# LDBiasDriver_CC_v2.net
KiCad netlist of a schematic drawn in EAGLE
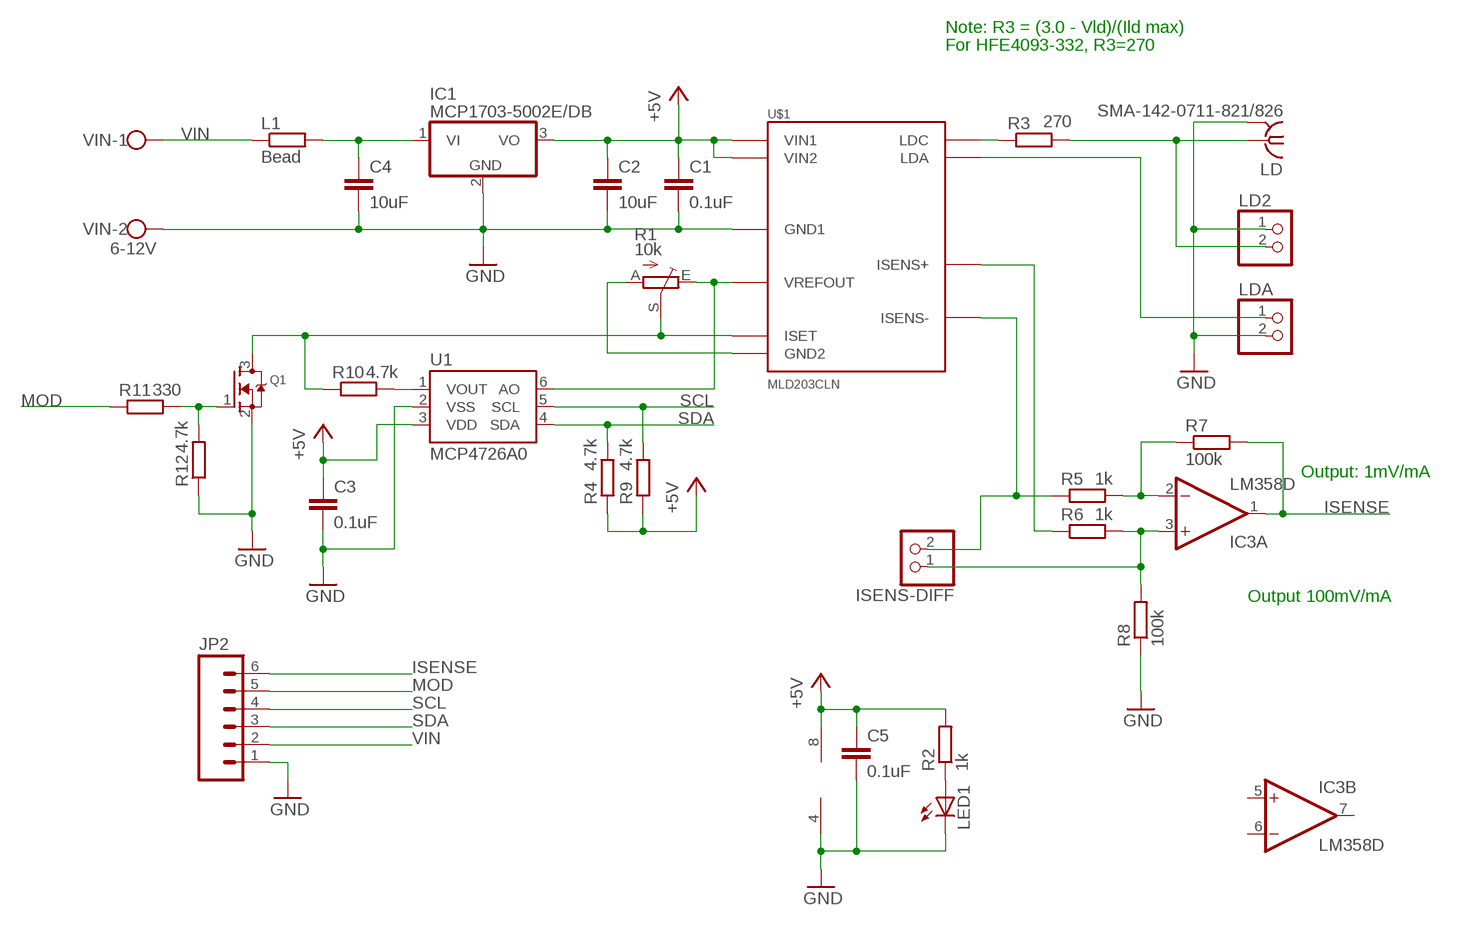
[diagram p0: schematic, sheet 1]

(export (version "E")
  (design (tool "Eeschema 10.0.6"))
  (components
    (comp (ref "C1")
      (value "0.1uF")
      (footprint "eagle-import:C0805")
      (libsource (lib "eagle-import") (part "C-EUC0805"))
    )
    (comp (ref "C2")
      (value "10uF")
      (footprint "eagle-import:C0805")
      (libsource (lib "eagle-import") (part "C-EUC0805"))
    )
    (comp (ref "C3")
      (value "0.1uF")
      (footprint "eagle-import:C0805")
      (libsource (lib "eagle-import") (part "C-EUC0805"))
    )
    (comp (ref "C4")
      (value "10uF")
      (footprint "eagle-import:C0805")
      (libsource (lib "eagle-import") (part "C-EUC0805"))
    )
    (comp (ref "C5")
      (value "0.1uF")
      (footprint "eagle-import:C0805")
      (libsource (lib "eagle-import") (part "C-EUC0805"))
    )
    (comp (ref "IC1")
      (value "MCP1703-5002E/DB")
      (footprint "eagle-import:SOT223")
      (libsource (lib "eagle-import") (part "MCP1703DB"))
    )
    (comp (ref "IC3")
      (value "LM358D")
      (footprint "eagle-import:SO08")
      (libsource (lib "eagle-import") (part "LM358D"))
    )
    (comp (ref "ISENS-DIFF")
      (value "PINHD-1X2")
      (footprint "eagle-import:1X02")
      (libsource (lib "eagle-import") (part "PINHD-1X2"))
    )
    (comp (ref "JP2")
      (value "M06POLAR_LOCK")
      (footprint "eagle-import:MOLEX-1X6_LOCK")
      (libsource (lib "eagle-import") (part "M06POLAR_LOCK"))
    )
    (comp (ref "L1")
      (value "Bead")
      (footprint "eagle-import:R0805")
      (libsource (lib "eagle-import") (part "R-EU_R0805"))
    )
    (comp (ref "LD")
      (value "SMA-142-0711-821/826")
      (footprint "eagle-import:J502-ND-142-0711-821_826")
      (fields (field (name "MF") "JOHNSON COMPONENTS") (field (name "MPN") "142-0711-821"))
      (libsource (lib "eagle-import") (part "SMA-142-0711-821/826"))
    )
    (comp (ref "LD2")
      (value "PINHD-1X2")
      (footprint "eagle-import:1X02")
      (libsource (lib "eagle-import") (part "PINHD-1X2"))
    )
    (comp (ref "LDA")
      (value "PINHD-1X2")
      (footprint "eagle-import:1X02")
      (libsource (lib "eagle-import") (part "PINHD-1X2"))
    )
    (comp (ref "LED1")
      (value "LEDCHIPLED_1206")
      (footprint "eagle-import:CHIPLED_1206")
      (libsource (lib "eagle-import") (part "LEDCHIPLED_1206"))
    )
    (comp (ref "Q1")
      (value "MOSFET-NREFLOW")
      (footprint "eagle-import:SOT23")
      (libsource (lib "eagle-import") (part "MOSFET-NREFLOW"))
    )
    (comp (ref "R1")
      (value "10k")
      (footprint "eagle-import:RJ9W")
      (libsource (lib "eagle-import") (part "TRIM_EU-RJ9W"))
    )
    (comp (ref "R2")
      (value "1k")
      (footprint "eagle-import:R0805")
      (libsource (lib "eagle-import") (part "R-EU_R0805"))
    )
    (comp (ref "R3")
      (value "270")
      (footprint "eagle-import:R0805")
      (libsource (lib "eagle-import") (part "R-EU_R0805"))
    )
    (comp (ref "R4")
      (value "4.7k")
      (footprint "eagle-import:R0805")
      (libsource (lib "eagle-import") (part "R-EU_R0805"))
    )
    (comp (ref "R5")
      (value "1k")
      (footprint "eagle-import:R0805")
      (libsource (lib "eagle-import") (part "R-EU_R0805"))
    )
    (comp (ref "R6")
      (value "1k")
      (footprint "eagle-import:R0805")
      (libsource (lib "eagle-import") (part "R-EU_R0805"))
    )
    (comp (ref "R7")
      (value "100k")
      (footprint "eagle-import:R0805")
      (libsource (lib "eagle-import") (part "R-EU_R0805"))
    )
    (comp (ref "R8")
      (value "100k")
      (footprint "eagle-import:R0805")
      (libsource (lib "eagle-import") (part "R-EU_R0805"))
    )
    (comp (ref "R9")
      (value "4.7k")
      (footprint "eagle-import:R0805")
      (libsource (lib "eagle-import") (part "R-EU_R0805"))
    )
    (comp (ref "R10")
      (value "4.7k")
      (footprint "eagle-import:R0805")
      (libsource (lib "eagle-import") (part "R-EU_R0805"))
    )
    (comp (ref "R11")
      (value "330")
      (footprint "eagle-import:R0805")
      (libsource (lib "eagle-import") (part "R-EU_R0805"))
    )
    (comp (ref "R12")
      (value "4.7k")
      (footprint "eagle-import:R0805")
      (libsource (lib "eagle-import") (part "R-EU_R0805"))
    )
    (comp (ref "U$1")
      (value "MLD203CLN")
      (footprint "eagle-import:MLD203")
      (libsource (lib "eagle-import") (part "MLD203CLN"))
    )
    (comp (ref "U1")
      (value "MCP4726A0")
      (footprint "eagle-import:SOT23-6")
      (libsource (lib "eagle-import") (part "MCP4725SOT-23"))
    )
    (comp (ref "VIN")
      (value "6-12V")
      (footprint "eagle-import:W237-102")
      (fields (field (name "MPN") "237-102"))
      (libsource (lib "eagle-import") (part "W237-102"))
    )
  )
  (nets
    (net (code "1") (name "+5V") (class "Default")
      (node (ref "C1") (pin "1") (pinfunction "1_1") (pintype "passive"))
      (node (ref "C2") (pin "1") (pinfunction "1_1") (pintype "passive"))
      (node (ref "C3") (pin "1") (pinfunction "1_1") (pintype "passive"))
      (node (ref "C5") (pin "1") (pinfunction "1_1") (pintype "passive"))
      (node (ref "IC1") (pin "3") (pinfunction "VO_3") (pintype "passive"))
      (node (ref "IC3") (pin "8") (pinfunction "V+_8") (pintype "power_in"))
      (node (ref "R2") (pin "2") (pinfunction "2_2") (pintype "passive"))
      (node (ref "R4") (pin "1") (pinfunction "1_1") (pintype "passive"))
      (node (ref "R9") (pin "1") (pinfunction "1_1") (pintype "passive"))
      (node (ref "U$1") (pin "P$1") (pinfunction "VIN1_P$1") (pintype "power_in"))
      (node (ref "U$1") (pin "P$2") (pinfunction "VIN2_P$2") (pintype "power_in"))
      (node (ref "U1") (pin "3") (pinfunction "VDD_3") (pintype "bidirectional"))
    )
    (net (code "2") (name "/ISENSE") (class "Default")
      (node (ref "IC3") (pin "1") (pinfunction "OUT_1") (pintype "output"))
      (node (ref "JP2") (pin "6") (pinfunction "6_6") (pintype "passive"))
      (node (ref "R7") (pin "2") (pinfunction "2_2") (pintype "passive"))
    )
    (net (code "3") (name "/MOD") (class "Default")
      (node (ref "JP2") (pin "5") (pinfunction "5_5") (pintype "passive"))
      (node (ref "R11") (pin "1") (pinfunction "1_1") (pintype "passive"))
    )
    (net (code "4") (name "/SCL") (class "Default")
      (node (ref "JP2") (pin "4") (pinfunction "4_4") (pintype "passive"))
      (node (ref "R9") (pin "2") (pinfunction "2_2") (pintype "passive"))
      (node (ref "U1") (pin "5") (pinfunction "SCL_5") (pintype "bidirectional"))
    )
    (net (code "5") (name "/SDA") (class "Default")
      (node (ref "JP2") (pin "3") (pinfunction "3_3") (pintype "passive"))
      (node (ref "R4") (pin "2") (pinfunction "2_2") (pintype "passive"))
      (node (ref "U1") (pin "4") (pinfunction "SDA_4") (pintype "bidirectional"))
    )
    (net (code "6") (name "/VIN") (class "Default")
      (node (ref "JP2") (pin "2") (pinfunction "2_2") (pintype "passive"))
      (node (ref "L1") (pin "1") (pinfunction "1_1") (pintype "passive"))
      (node (ref "VIN") (pin "1") (pinfunction "KL_1") (pintype "passive"))
    )
    (net (code "7") (name "GND") (class "Default")
      (node (ref "C1") (pin "2") (pinfunction "2_2") (pintype "passive"))
      (node (ref "C2") (pin "2") (pinfunction "2_2") (pintype "passive"))
      (node (ref "C3") (pin "2") (pinfunction "2_2") (pintype "passive"))
      (node (ref "C4") (pin "2") (pinfunction "2_2") (pintype "passive"))
      (node (ref "C5") (pin "2") (pinfunction "2_2") (pintype "passive"))
      (node (ref "IC1") (pin "2") (pinfunction "GND_2") (pintype "passive"))
      (node (ref "IC3") (pin "4") (pinfunction "V-_4") (pintype "power_in"))
      (node (ref "JP2") (pin "1") (pinfunction "1_1") (pintype "passive"))
      (node (ref "LD") (pin "G@1") (pinfunction "2_G@1") (pintype "passive"))
      (node (ref "LD") (pin "G@2") (pinfunction "2_G@2") (pintype "passive"))
      (node (ref "LD") (pin "G@3") (pinfunction "2_G@3") (pintype "passive"))
      (node (ref "LD") (pin "G@4") (pinfunction "2_G@4") (pintype "passive"))
      (node (ref "LD2") (pin "1") (pinfunction "1_1") (pintype "passive"))
      (node (ref "LDA") (pin "2") (pinfunction "2_2") (pintype "passive"))
      (node (ref "LED1") (pin "C") (pinfunction "C_C") (pintype "passive"))
      (node (ref "Q1") (pin "2") (pinfunction "S_2") (pintype "bidirectional"))
      (node (ref "R12") (pin "1") (pinfunction "1_1") (pintype "passive"))
      (node (ref "R8") (pin "1") (pinfunction "1_1") (pintype "passive"))
      (node (ref "U$1") (pin "P$3") (pinfunction "GND1_P$3") (pintype "power_in"))
      (node (ref "U1") (pin "2") (pinfunction "VSS_2") (pintype "bidirectional"))
      (node (ref "VIN") (pin "2") (pinfunction "KL_2") (pintype "passive"))
    )
    (net (code "8") (name "Net-(IC1-VI)") (class "Default")
      (node (ref "C4") (pin "1") (pinfunction "1_1") (pintype "passive"))
      (node (ref "IC1") (pin "1") (pinfunction "VI_1") (pintype "input"))
      (node (ref "L1") (pin "2") (pinfunction "2_2") (pintype "passive"))
    )
    (net (code "9") (name "Net-(IC3A-+IN)") (class "Default")
      (node (ref "IC3") (pin "3") (pinfunction "+IN_3") (pintype "input"))
      (node (ref "ISENS-DIFF") (pin "1") (pinfunction "1_1") (pintype "passive"))
      (node (ref "R6") (pin "2") (pinfunction "2_2") (pintype "passive"))
      (node (ref "R8") (pin "2") (pinfunction "2_2") (pintype "passive"))
    )
    (net (code "10") (name "Net-(IC3A--IN)") (class "Default")
      (node (ref "IC3") (pin "2") (pinfunction "-IN_2") (pintype "input"))
      (node (ref "R5") (pin "2") (pinfunction "2_2") (pintype "passive"))
      (node (ref "R7") (pin "1") (pinfunction "1_1") (pintype "passive"))
    )
    (net (code "11") (name "Net-(LD-Pad1)") (class "Default")
      (node (ref "LD") (pin "1") (pinfunction "1_1") (pintype "passive"))
      (node (ref "LD2") (pin "2") (pinfunction "2_2") (pintype "passive"))
      (node (ref "R3") (pin "2") (pinfunction "2_2") (pintype "passive"))
    )
    (net (code "12") (name "Net-(LED1-PadA)") (class "Default")
      (node (ref "LED1") (pin "A") (pinfunction "A_A") (pintype "passive"))
      (node (ref "R2") (pin "1") (pinfunction "1_1") (pintype "passive"))
    )
    (net (code "13") (name "Net-(Q1-D)") (class "Default")
      (node (ref "Q1") (pin "3") (pinfunction "D_3") (pintype "bidirectional"))
      (node (ref "R1") (pin "S") (pinfunction "S_S") (pintype "passive"))
      (node (ref "R10") (pin "1") (pinfunction "1_1") (pintype "passive"))
      (node (ref "U$1") (pin "P$6") (pinfunction "ISET_P$6") (pintype "bidirectional"))
    )
    (net (code "14") (name "Net-(Q1-G)") (class "Default")
      (node (ref "Q1") (pin "1") (pinfunction "G_1") (pintype "bidirectional"))
      (node (ref "R11") (pin "2") (pinfunction "2_2") (pintype "passive"))
      (node (ref "R12") (pin "2") (pinfunction "2_2") (pintype "passive"))
    )
    (net (code "15") (name "Net-(U$1-GND2)") (class "Default")
      (node (ref "R1") (pin "A") (pinfunction "A_A") (pintype "passive"))
      (node (ref "U$1") (pin "P$4") (pinfunction "GND2_P$4") (pintype "power_in"))
    )
    (net (code "16") (name "Net-(U$1-ISENS+)") (class "Default")
      (node (ref "R6") (pin "1") (pinfunction "1_1") (pintype "passive"))
      (node (ref "U$1") (pin "P$12") (pinfunction "ISENS+_P$12") (pintype "bidirectional"))
    )
    (net (code "17") (name "Net-(U$1-ISENS-)") (class "Default")
      (node (ref "ISENS-DIFF") (pin "2") (pinfunction "2_2") (pintype "passive"))
      (node (ref "R5") (pin "1") (pinfunction "1_1") (pintype "passive"))
      (node (ref "U$1") (pin "P$13") (pinfunction "ISENS-_P$13") (pintype "bidirectional"))
    )
    (net (code "18") (name "Net-(U$1-LDA)") (class "Default")
      (node (ref "LDA") (pin "1") (pinfunction "1_1") (pintype "passive"))
      (node (ref "U$1") (pin "P$14") (pinfunction "LDA_P$14") (pintype "bidirectional"))
    )
    (net (code "19") (name "Net-(U$1-LDC)") (class "Default")
      (node (ref "R3") (pin "1") (pinfunction "1_1") (pintype "passive"))
      (node (ref "U$1") (pin "P$11") (pinfunction "LDC_P$11") (pintype "bidirectional"))
    )
    (net (code "20") (name "Net-(U$1-VREFOUT)") (class "Default")
      (node (ref "R1") (pin "E") (pinfunction "E_E") (pintype "passive"))
      (node (ref "U$1") (pin "P$5") (pinfunction "VREFOUT_P$5") (pintype "bidirectional"))
      (node (ref "U1") (pin "6") (pinfunction "AO_6") (pintype "bidirectional"))
    )
    (net (code "21") (name "Net-(U1-VOUT)") (class "Default")
      (node (ref "R10") (pin "2") (pinfunction "2_2") (pintype "passive"))
      (node (ref "U1") (pin "1") (pinfunction "VOUT_1") (pintype "bidirectional"))
    )
    (net (code "22") (name "unconnected-(IC3B-+IN-Pad5)") (class "Default")
      (node (ref "IC3") (pin "5") (pinfunction "+IN_5") (pintype "input"))
    )
    (net (code "23") (name "unconnected-(IC3B--IN-Pad6)") (class "Default")
      (node (ref "IC3") (pin "6") (pinfunction "-IN_6") (pintype "input"))
    )
    (net (code "24") (name "unconnected-(IC3B-OUT-Pad7)") (class "Default")
      (node (ref "IC3") (pin "7") (pinfunction "OUT_7") (pintype "output"))
    )
  )
)
